# Schematic_-_Ebook_Reader_vFinal_v37.net
KiCad netlist of a schematic drawn in EAGLE
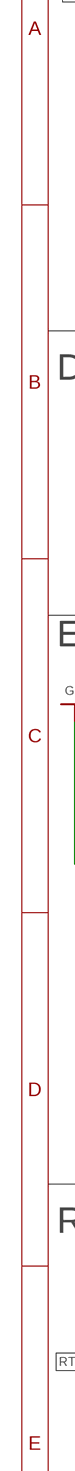
[diagram p0: schematic, sheet 1, part 1 of 2]
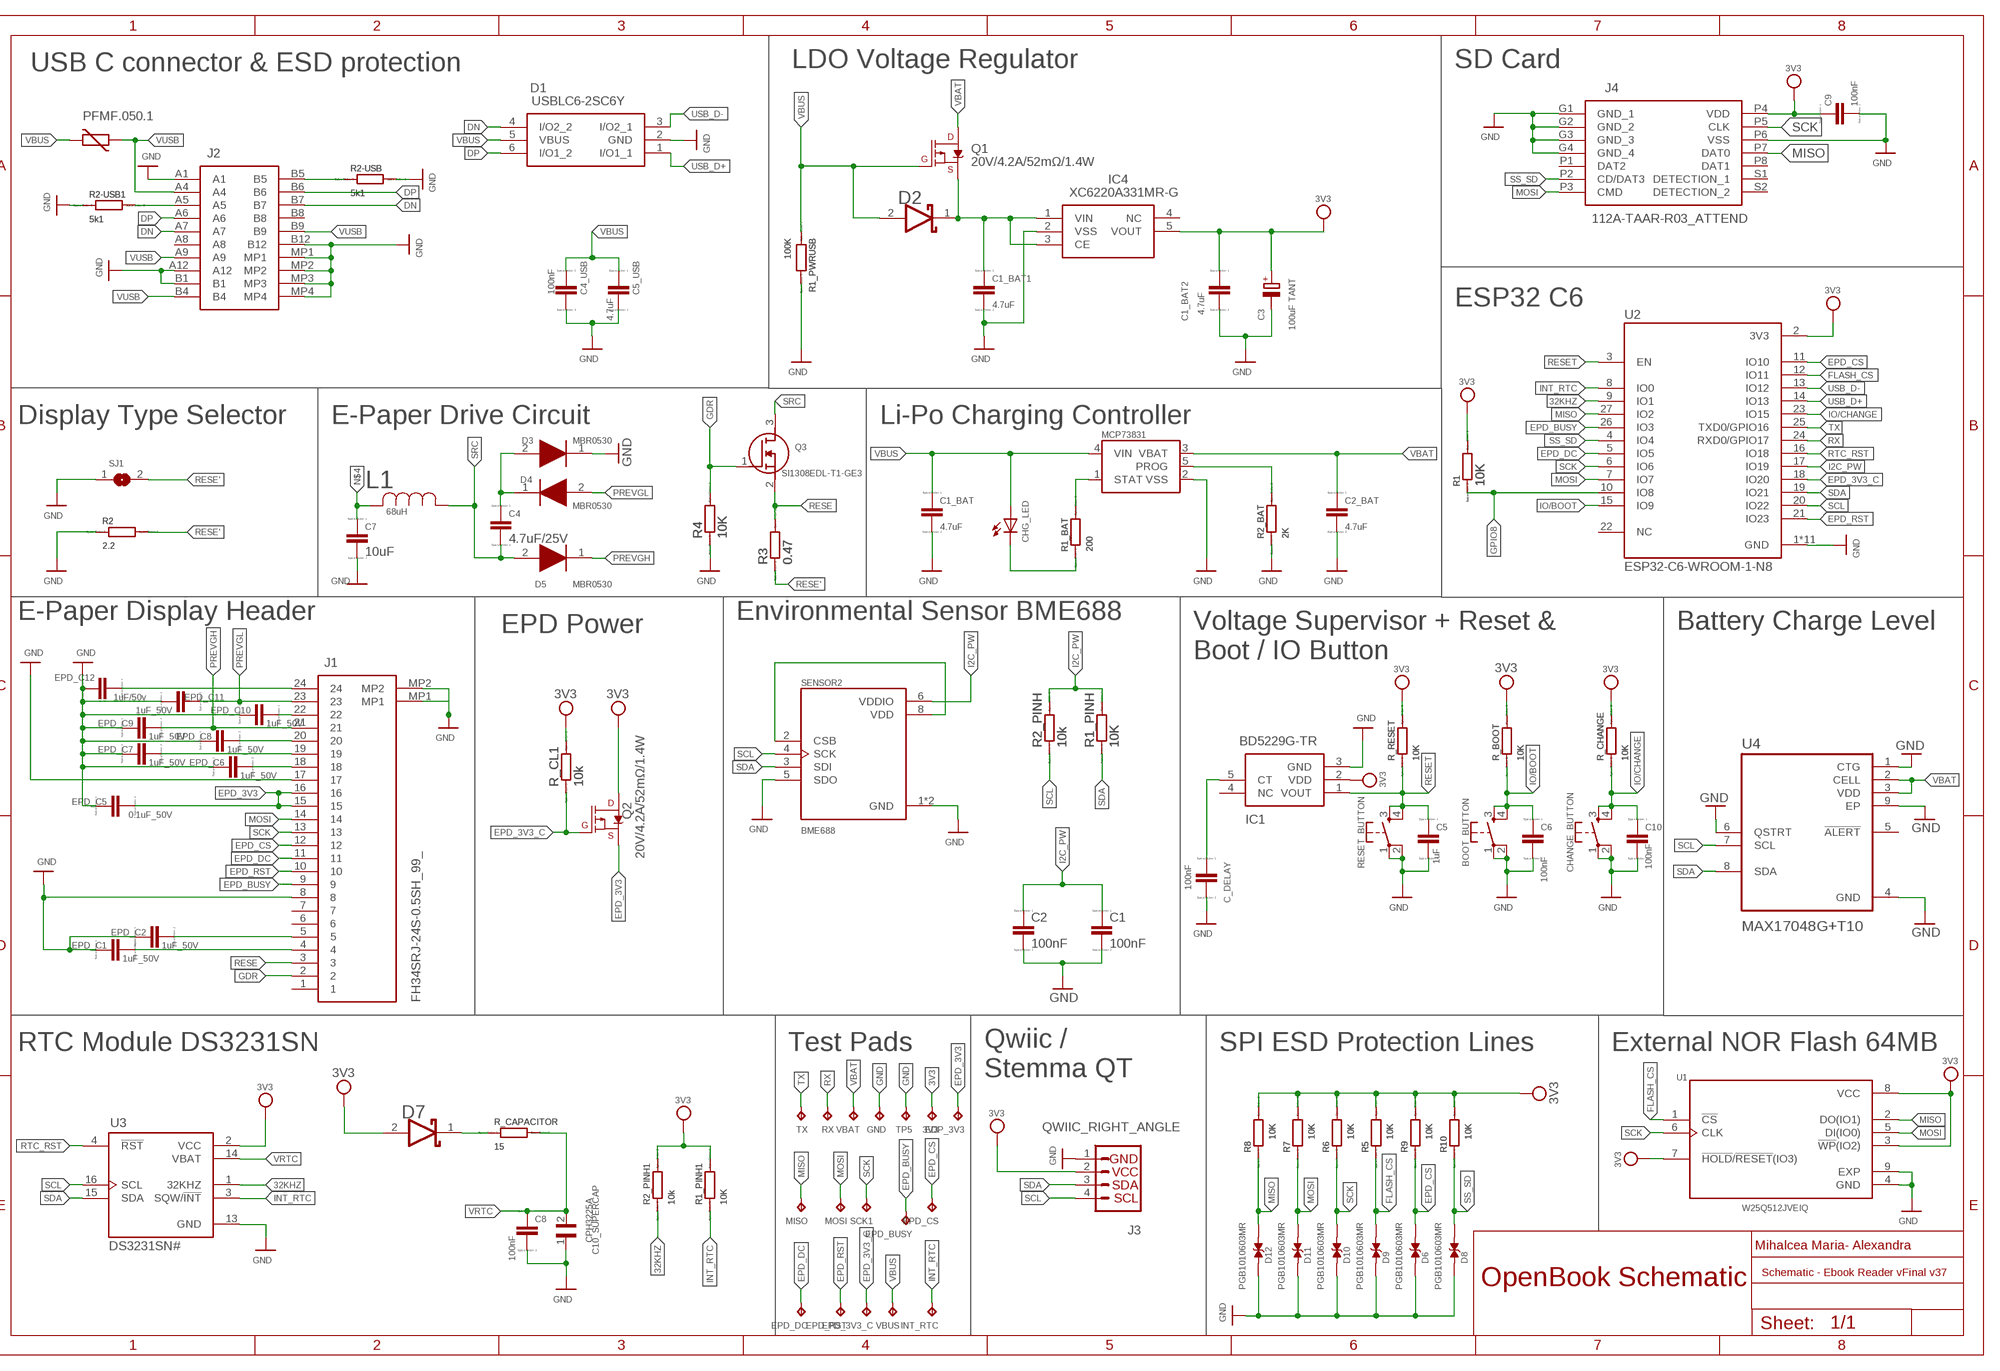
[diagram p1: schematic, sheet 1, part 2 of 2]

(export (version "E")
  (design (tool "Eeschema 10.0.6"))
  (components
    (comp (ref "3V3")
      (value "TPTP20R")
      (footprint "eagle-import:TP20R")
      (libsource (lib "eagle-import") (part "TPTP20R"))
    )
    (comp (ref "BOOT_BUTTON")
      (value "BUTTON_CUSYOMV1")
      (footprint "eagle-import:MYBUTTON")
      (libsource (lib "eagle-import") (part "BUTTON_CUSYOMV1"))
    )
    (comp (ref "C1")
      (value "100nF")
      (footprint "eagle-import:EAGLE-LTSPICE_C0402")
      (libsource (lib "eagle-import") (part "EAGLE-LTSPICE_CC0402"))
    )
    (comp (ref "C1_BAT")
      (value "4.7uF")
      (footprint "eagle-import:EAGLE-LTSPICE_C0402")
      (libsource (lib "eagle-import") (part "EAGLE-LTSPICE_CC0402"))
    )
    (comp (ref "C1_BAT1")
      (value "4.7uF")
      (footprint "eagle-import:EAGLE-LTSPICE_C0402")
      (libsource (lib "eagle-import") (part "EAGLE-LTSPICE_CC0402"))
    )
    (comp (ref "C1_BAT2")
      (value "4.7uF")
      (footprint "eagle-import:EAGLE-LTSPICE_C0402")
      (libsource (lib "eagle-import") (part "EAGLE-LTSPICE_CC0402"))
    )
    (comp (ref "C2")
      (value "100nF")
      (footprint "eagle-import:EAGLE-LTSPICE_C0402")
      (libsource (lib "eagle-import") (part "EAGLE-LTSPICE_CC0402"))
    )
    (comp (ref "C2_BAT")
      (value "4.7uF")
      (footprint "eagle-import:EAGLE-LTSPICE_C0402")
      (libsource (lib "eagle-import") (part "EAGLE-LTSPICE_CC0402"))
    )
    (comp (ref "C3")
      (value "100uF TANT")
      (footprint "eagle-import:RCL_CT3528")
      (libsource (lib "eagle-import") (part "RCL_CPOL-EUCT3528"))
    )
    (comp (ref "C4")
      (value "4.7uF/25V")
      (footprint "eagle-import:EAGLE-LTSPICE_C0402")
      (libsource (lib "eagle-import") (part "EAGLE-LTSPICE_CC0402"))
    )
    (comp (ref "C4_USB")
      (value "100nF")
      (footprint "eagle-import:EAGLE-LTSPICE_C0402")
      (libsource (lib "eagle-import") (part "EAGLE-LTSPICE_CC0402"))
    )
    (comp (ref "C5")
      (value "1uF")
      (footprint "eagle-import:EAGLE-LTSPICE_C0402")
      (libsource (lib "eagle-import") (part "EAGLE-LTSPICE_CC0402"))
    )
    (comp (ref "C5_USB")
      (value "4.7uF")
      (footprint "eagle-import:EAGLE-LTSPICE_C0402")
      (libsource (lib "eagle-import") (part "EAGLE-LTSPICE_CC0402"))
    )
    (comp (ref "C6")
      (value "100nF")
      (footprint "eagle-import:EAGLE-LTSPICE_C0402")
      (libsource (lib "eagle-import") (part "EAGLE-LTSPICE_CC0402"))
    )
    (comp (ref "C7")
      (value "10uF")
      (footprint "eagle-import:EAGLE-LTSPICE_C0402")
      (libsource (lib "eagle-import") (part "EAGLE-LTSPICE_CC0402"))
    )
    (comp (ref "C8")
      (value "100nF")
      (footprint "eagle-import:EAGLE-LTSPICE_C0402")
      (libsource (lib "eagle-import") (part "EAGLE-LTSPICE_CC0402"))
    )
    (comp (ref "C9")
      (value "100nF")
      (footprint "eagle-import:EAGLE-LTSPICE_C0402")
      (libsource (lib "eagle-import") (part "EAGLE-LTSPICE_CC0402"))
    )
    (comp (ref "C10")
      (value "100nF")
      (footprint "eagle-import:EAGLE-LTSPICE_C0402")
      (libsource (lib "eagle-import") (part "EAGLE-LTSPICE_CC0402"))
    )
    (comp (ref "C10_SUPERCAP")
      (value "CPH3225A")
      (footprint "eagle-import:CAPCP3225X100N")
      (fields (field (name "MF") "Seiko Instruments"))
      (libsource (lib "eagle-import") (part "CPH3225A"))
    )
    (comp (ref "CHANGE_BUTTON")
      (value "BUTTON_CUSYOMV1")
      (footprint "eagle-import:MYBUTTON")
      (libsource (lib "eagle-import") (part "BUTTON_CUSYOMV1"))
    )
    (comp (ref "CHG_LED")
      (value "ADAFRUIT_LEDCHIP-LED0603")
      (footprint "eagle-import:ADAFRUIT_CHIP-LED0603")
      (libsource (lib "eagle-import") (part "ADAFRUIT_LEDCHIP-LED0603"))
    )
    (comp (ref "C_DELAY")
      (value "100nF")
      (footprint "eagle-import:EAGLE-LTSPICE_C0402")
      (libsource (lib "eagle-import") (part "EAGLE-LTSPICE_CC0402"))
    )
    (comp (ref "D1")
      (value "USBLC6-2SC6Y")
      (footprint "eagle-import:SOT95P280X145-6N")
      (fields (field (name "MF") "STMicroelectronics"))
      (libsource (lib "eagle-import") (part "USBLC6-2SC6Y"))
    )
    (comp (ref "D2")
      (value "ESP32_WROVER_AVX---SD0805S020S1R0_AVX_SD0805S020S1R0_0_0AVX_SD0805S020S1R0_0_0")
      (footprint "eagle-import:ESP32_WROVER_AVX---SD0805S020S1R0_AVX_SD0805S020S1R0_0")
      (fields
        (field (name "DIGIKEY_PART_NUMBER") "478-7800-1-ND")
        (field (name "MF") "AVX")
        (field (name "MOUSER_PART_NUMBER") "581-SD0805S020S1R0")
      )
      (libsource (lib "eagle-import") (part "ESP32_WROVER_AVX---SD0805S020S1R0_AVX_SD0805S020S1R0_0_0AVX_SD0805S020S1R0_0_0"))
    )
    (comp (ref "D3")
      (value "MBR0530")
      (footprint "eagle-import:SOD3716X135N")
      (fields (field (name "MF") "ON Semiconductor"))
      (libsource (lib "eagle-import") (part "MBR0530"))
    )
    (comp (ref "D4")
      (value "MBR0530")
      (footprint "eagle-import:SOD3716X135N")
      (fields (field (name "MF") "ON Semiconductor"))
      (libsource (lib "eagle-import") (part "MBR0530"))
    )
    (comp (ref "D5")
      (value "MBR0530")
      (footprint "eagle-import:SOD3716X135N")
      (fields (field (name "MF") "ON Semiconductor"))
      (libsource (lib "eagle-import") (part "MBR0530"))
    )
    (comp (ref "D6")
      (value "PGB1010603MR")
      (footprint "eagle-import:DIOC1608X36N")
      (fields (field (name "MF") "Littelfuse Inc."))
      (libsource (lib "eagle-import") (part "PGB1010603MR"))
    )
    (comp (ref "D7")
      (value "ESP32_WROVER_AVX---SD0805S020S1R0_AVX_SD0805S020S1R0_0_0AVX_SD0805S020S1R0_0_0")
      (footprint "eagle-import:ESP32_WROVER_AVX---SD0805S020S1R0_AVX_SD0805S020S1R0_0")
      (fields
        (field (name "DIGIKEY_PART_NUMBER") "478-7800-1-ND")
        (field (name "MF") "AVX")
        (field (name "MOUSER_PART_NUMBER") "581-SD0805S020S1R0")
      )
      (libsource (lib "eagle-import") (part "ESP32_WROVER_AVX---SD0805S020S1R0_AVX_SD0805S020S1R0_0_0AVX_SD0805S020S1R0_0_0"))
    )
    (comp (ref "D8")
      (value "PGB1010603MR")
      (footprint "eagle-import:DIOC1608X36N")
      (fields (field (name "MF") "Littelfuse Inc."))
      (libsource (lib "eagle-import") (part "PGB1010603MR"))
    )
    (comp (ref "D9")
      (value "PGB1010603MR")
      (footprint "eagle-import:DIOC1608X36N")
      (fields (field (name "MF") "Littelfuse Inc."))
      (libsource (lib "eagle-import") (part "PGB1010603MR"))
    )
    (comp (ref "D10")
      (value "PGB1010603MR")
      (footprint "eagle-import:DIOC1608X36N")
      (fields (field (name "MF") "Littelfuse Inc."))
      (libsource (lib "eagle-import") (part "PGB1010603MR"))
    )
    (comp (ref "D11")
      (value "PGB1010603MR")
      (footprint "eagle-import:DIOC1608X36N")
      (fields (field (name "MF") "Littelfuse Inc."))
      (libsource (lib "eagle-import") (part "PGB1010603MR"))
    )
    (comp (ref "D12")
      (value "PGB1010603MR")
      (footprint "eagle-import:DIOC1608X36N")
      (fields (field (name "MF") "Littelfuse Inc."))
      (libsource (lib "eagle-import") (part "PGB1010603MR"))
    )
    (comp (ref "EDP_3V3")
      (value "TPTP20R")
      (footprint "eagle-import:TP20R")
      (libsource (lib "eagle-import") (part "TPTP20R"))
    )
    (comp (ref "EPD_3V3_C")
      (value "TPTP20R")
      (footprint "eagle-import:TP20R")
      (libsource (lib "eagle-import") (part "TPTP20R"))
    )
    (comp (ref "EPD_BUSY")
      (value "TPTP20R")
      (footprint "eagle-import:TP20R")
      (libsource (lib "eagle-import") (part "TPTP20R"))
    )
    (comp (ref "EPD_C1")
      (value "1uF_50V")
      (footprint "eagle-import:EAGLE-LTSPICE_C0402")
      (libsource (lib "eagle-import") (part "EAGLE-LTSPICE_CC0402"))
    )
    (comp (ref "EPD_C2")
      (value "1uF_50V")
      (footprint "eagle-import:EAGLE-LTSPICE_C0402")
      (libsource (lib "eagle-import") (part "EAGLE-LTSPICE_CC0402"))
    )
    (comp (ref "EPD_C5")
      (value "0.1uF_50V")
      (footprint "eagle-import:EAGLE-LTSPICE_C0402")
      (libsource (lib "eagle-import") (part "EAGLE-LTSPICE_CC0402"))
    )
    (comp (ref "EPD_C6")
      (value "1uF_50V")
      (footprint "eagle-import:EAGLE-LTSPICE_C0402")
      (libsource (lib "eagle-import") (part "EAGLE-LTSPICE_CC0402"))
    )
    (comp (ref "EPD_C7")
      (value "1uF_50V")
      (footprint "eagle-import:EAGLE-LTSPICE_C0402")
      (libsource (lib "eagle-import") (part "EAGLE-LTSPICE_CC0402"))
    )
    (comp (ref "EPD_C8")
      (value "1uF_50V")
      (footprint "eagle-import:EAGLE-LTSPICE_C0402")
      (libsource (lib "eagle-import") (part "EAGLE-LTSPICE_CC0402"))
    )
    (comp (ref "EPD_C9")
      (value "1uF_50V")
      (footprint "eagle-import:EAGLE-LTSPICE_C0402")
      (libsource (lib "eagle-import") (part "EAGLE-LTSPICE_CC0402"))
    )
    (comp (ref "EPD_C10")
      (value "1uF_50V")
      (footprint "eagle-import:EAGLE-LTSPICE_C0402")
      (libsource (lib "eagle-import") (part "EAGLE-LTSPICE_CC0402"))
    )
    (comp (ref "EPD_C11")
      (value "1uF_50V")
      (footprint "eagle-import:EAGLE-LTSPICE_C0402")
      (libsource (lib "eagle-import") (part "EAGLE-LTSPICE_CC0402"))
    )
    (comp (ref "EPD_C12")
      (value "1uF/50v")
      (footprint "eagle-import:EAGLE-LTSPICE_C0402")
      (libsource (lib "eagle-import") (part "EAGLE-LTSPICE_CC0402"))
    )
    (comp (ref "EPD_CS")
      (value "TPTP20R")
      (footprint "eagle-import:TP20R")
      (libsource (lib "eagle-import") (part "TPTP20R"))
    )
    (comp (ref "EPD_DC")
      (value "TPTP20R")
      (footprint "eagle-import:TP20R")
      (libsource (lib "eagle-import") (part "TPTP20R"))
    )
    (comp (ref "EPD_RST")
      (value "TPTP20R")
      (footprint "eagle-import:TP20R")
      (libsource (lib "eagle-import") (part "TPTP20R"))
    )
    (comp (ref "GND")
      (value "TPTP20R")
      (footprint "eagle-import:TP20R")
      (libsource (lib "eagle-import") (part "TPTP20R"))
    )
    (comp (ref "IC1")
      (value "BD5229G-TR")
      (footprint "eagle-import:SOT95P280X125-5N")
      (fields (field (name "MOUSER_PART_NUMBER") "755-BD5229G-TR"))
      (libsource (lib "eagle-import") (part "BD5229G-TR"))
    )
    (comp (ref "IC4")
      (value "XC6220A331MR-G")
      (footprint "eagle-import:SOT95P280X120-5N")
      (fields (field (name "MOUSER_PART_NUMBER") "865-XC6220A331MR-G"))
      (libsource (lib "eagle-import") (part "XC6220A331MR-G"))
    )
    (comp (ref "INT_RTC")
      (value "TPTP20R")
      (footprint "eagle-import:TP20R")
      (libsource (lib "eagle-import") (part "TPTP20R"))
    )
    (comp (ref "J1")
      (value "FH34SRJ-24S-0.5SH_99_")
      (footprint "eagle-import:FH34SRJ24S05SH99")
      (fields
        (field (name "MANUFACTURER_PART_NUMBER") "FH34SRJ-24S-0.5SH(99)")
        (field (name "MOUSER_PART_NUMBER") "798-FH34SRJ24S05SH99")
      )
      (libsource (lib "eagle-import") (part "FH34SRJ-24S-0.5SH_99_"))
    )
    (comp (ref "J2")
      (value "SAMACSYS_PARTS_USB4110-GF-A")
      (footprint "eagle-import:SAMACSYS_PARTS_USB4110GFA")
      (fields
        (field (name "MANUFACTURER_PART_NUMBER") "USB4110-GF-A")
        (field (name "MOUSER_PART_NUMBER") "640-USB4110-GF-A")
      )
      (libsource (lib "eagle-import") (part "SAMACSYS_PARTS_USB4110-GF-A"))
    )
    (comp (ref "J3")
      (value "QWIIC_RIGHT_ANGLE")
      (footprint "eagle-import:JST04_1MM_RA")
      (libsource (lib "eagle-import") (part "QWIIC_CONNECTORJS-1MM"))
    )
    (comp (ref "J4")
      (value "112A-TAAR-R03_ATTEND")
      (footprint "eagle-import:112ATAARR03ATTEND")
      (fields (field (name "MANUFACTURER_PART_NUMBER") "112A-TAAR-R03 ATTEND"))
      (libsource (lib "eagle-import") (part "112A-TAAR-R03_ATTEND"))
    )
    (comp (ref "L1")
      (value "68uH")
      (footprint "eagle-import:IND_4828-WE-TPC_WRE")
      (fields
        (field (name "MANUFACTURER_PART_NUMBER") "744043680")
        (field (name "COPYRIGHT") "Copyright (C) 2024 Ultra Librarian. All rights reserved.")
      )
      (libsource (lib "eagle-import") (part "744043680IND_4828-WE-TPC_WRE"))
    )
    (comp (ref "MCP73831")
      (value "ESP32_WROVER_SPARKFUN-IC-POWER_MCP73831")
      (footprint "eagle-import:ESP32_WROVER_SPARKFUN-IC-POWER_SOT23-5")
      (libsource (lib "eagle-import") (part "ESP32_WROVER_SPARKFUN-IC-POWER_MCP73831"))
    )
    (comp (ref "MISO")
      (value "TPTP20R")
      (footprint "eagle-import:TP20R")
      (libsource (lib "eagle-import") (part "TPTP20R"))
    )
    (comp (ref "MOSI")
      (value "TPTP20R")
      (footprint "eagle-import:TP20R")
      (libsource (lib "eagle-import") (part "TPTP20R"))
    )
    (comp (ref "PFMF.050.1")
      (value "ESP32C6_VARISTORCN1812")
      (footprint "eagle-import:ESP32C6_VARISTOR_CT_CN1812")
      (libsource (lib "eagle-import") (part "ESP32C6_VARISTORCN1812"))
    )
    (comp (ref "Q1")
      (value "20V/4.2A/52mΩ/1.4W")
      (footprint "eagle-import:ESP32_WROVER_SPARKFUN-DISCRETESEMI_SOT23-3")
      (libsource (lib "eagle-import") (part "ESP32_WROVER_SPARKFUN-DISCRETESEMI_MOSFET_PCH-DMG2305UX-7"))
    )
    (comp (ref "Q2")
      (value "20V/4.2A/52mΩ/1.4W")
      (footprint "eagle-import:ESP32_WROVER_SPARKFUN-DISCRETESEMI_SOT23-3")
      (libsource (lib "eagle-import") (part "ESP32_WROVER_SPARKFUN-DISCRETESEMI_MOSFET_PCH-DMG2305UX-7"))
    )
    (comp (ref "Q3")
      (value "SI1308EDL-T1-GE3")
      (footprint "eagle-import:SOT65P210X110-3N")
      (fields (field (name "MF") "Vishay Siliconix"))
      (libsource (lib "eagle-import") (part "SI1308EDL-T1-GE3"))
    )
    (comp (ref "R1")
      (value "10K")
      (footprint "eagle-import:ESP32_WROVER_EAGLE-LTSPICE_R0402")
      (libsource (lib "eagle-import") (part "ESP32_WROVER_EAGLE-LTSPICE_RR0402"))
    )
    (comp (ref "R1_BAT")
      (value "200")
      (footprint "eagle-import:ESP32_WROVER_EAGLE-LTSPICE_R0402")
      (libsource (lib "eagle-import") (part "ESP32_WROVER_EAGLE-LTSPICE_RR0402"))
    )
    (comp (ref "R1_PINH")
      (value "10K")
      (footprint "eagle-import:ESP32_WROVER_EAGLE-LTSPICE_R0402")
      (libsource (lib "eagle-import") (part "ESP32_WROVER_EAGLE-LTSPICE_RR0402"))
    )
    (comp (ref "R1_PINH1")
      (value "10K")
      (footprint "eagle-import:ESP32_WROVER_EAGLE-LTSPICE_R0402")
      (libsource (lib "eagle-import") (part "ESP32_WROVER_EAGLE-LTSPICE_RR0402"))
    )
    (comp (ref "R1_PWRUSB")
      (value "100K")
      (footprint "eagle-import:ESP32_WROVER_EAGLE-LTSPICE_R0402")
      (libsource (lib "eagle-import") (part "ESP32_WROVER_EAGLE-LTSPICE_RR0402"))
    )
    (comp (ref "R2")
      (value "2.2")
      (footprint "eagle-import:ESP32_WROVER_EAGLE-LTSPICE_R0402")
      (libsource (lib "eagle-import") (part "ESP32_WROVER_EAGLE-LTSPICE_RR0402"))
    )
    (comp (ref "R2-USB")
      (value "5k1")
      (footprint "eagle-import:ESP32_WROVER_EAGLE-LTSPICE_R0402")
      (libsource (lib "eagle-import") (part "ESP32_WROVER_EAGLE-LTSPICE_RR0402"))
    )
    (comp (ref "R2-USB1")
      (value "5k1")
      (footprint "eagle-import:ESP32_WROVER_EAGLE-LTSPICE_R0402")
      (libsource (lib "eagle-import") (part "ESP32_WROVER_EAGLE-LTSPICE_RR0402"))
    )
    (comp (ref "R2_BAT")
      (value "2K")
      (footprint "eagle-import:ESP32_WROVER_EAGLE-LTSPICE_R0402")
      (libsource (lib "eagle-import") (part "ESP32_WROVER_EAGLE-LTSPICE_RR0402"))
    )
    (comp (ref "R2_PINH")
      (value "10k")
      (footprint "eagle-import:ESP32_WROVER_EAGLE-LTSPICE_R0402")
      (libsource (lib "eagle-import") (part "ESP32_WROVER_EAGLE-LTSPICE_RR0402"))
    )
    (comp (ref "R2_PINH1")
      (value "10k")
      (footprint "eagle-import:ESP32_WROVER_EAGLE-LTSPICE_R0402")
      (libsource (lib "eagle-import") (part "ESP32_WROVER_EAGLE-LTSPICE_RR0402"))
    )
    (comp (ref "R3")
      (value "0.47")
      (footprint "eagle-import:ESP32_WROVER_EAGLE-LTSPICE_R0402")
      (libsource (lib "eagle-import") (part "ESP32_WROVER_EAGLE-LTSPICE_RR0402"))
    )
    (comp (ref "R4")
      (value "10K")
      (footprint "eagle-import:ESP32_WROVER_EAGLE-LTSPICE_R0402")
      (libsource (lib "eagle-import") (part "ESP32_WROVER_EAGLE-LTSPICE_RR0402"))
    )
    (comp (ref "R5")
      (value "10K")
      (footprint "eagle-import:ESP32_WROVER_EAGLE-LTSPICE_R0402")
      (libsource (lib "eagle-import") (part "ESP32_WROVER_EAGLE-LTSPICE_RR0402"))
    )
    (comp (ref "R6")
      (value "10K")
      (footprint "eagle-import:ESP32_WROVER_EAGLE-LTSPICE_R0402")
      (libsource (lib "eagle-import") (part "ESP32_WROVER_EAGLE-LTSPICE_RR0402"))
    )
    (comp (ref "R7")
      (value "10K")
      (footprint "eagle-import:ESP32_WROVER_EAGLE-LTSPICE_R0402")
      (libsource (lib "eagle-import") (part "ESP32_WROVER_EAGLE-LTSPICE_RR0402"))
    )
    (comp (ref "R8")
      (value "10K")
      (footprint "eagle-import:ESP32_WROVER_EAGLE-LTSPICE_R0402")
      (libsource (lib "eagle-import") (part "ESP32_WROVER_EAGLE-LTSPICE_RR0402"))
    )
    (comp (ref "R9")
      (value "10K")
      (footprint "eagle-import:ESP32_WROVER_EAGLE-LTSPICE_R0402")
      (libsource (lib "eagle-import") (part "ESP32_WROVER_EAGLE-LTSPICE_RR0402"))
    )
    (comp (ref "R10")
      (value "10K")
      (footprint "eagle-import:ESP32_WROVER_EAGLE-LTSPICE_R0402")
      (libsource (lib "eagle-import") (part "ESP32_WROVER_EAGLE-LTSPICE_RR0402"))
    )
    (comp (ref "RESET_BUTTON")
      (value "BUTTON_CUSYOMV1")
      (footprint "eagle-import:MYBUTTON")
      (libsource (lib "eagle-import") (part "BUTTON_CUSYOMV1"))
    )
    (comp (ref "RX")
      (value "TPTP20R")
      (footprint "eagle-import:TP20R")
      (libsource (lib "eagle-import") (part "TPTP20R"))
    )
    (comp (ref "R_BOOT")
      (value "10K")
      (footprint "eagle-import:ESP32_WROVER_EAGLE-LTSPICE_R0402")
      (libsource (lib "eagle-import") (part "ESP32_WROVER_EAGLE-LTSPICE_RR0402"))
    )
    (comp (ref "R_CAPACITOR")
      (value "15")
      (footprint "eagle-import:ESP32_WROVER_EAGLE-LTSPICE_R0402")
      (libsource (lib "eagle-import") (part "ESP32_WROVER_EAGLE-LTSPICE_RR0402"))
    )
    (comp (ref "R_CHANGE")
      (value "10K")
      (footprint "eagle-import:ESP32_WROVER_EAGLE-LTSPICE_R0402")
      (libsource (lib "eagle-import") (part "ESP32_WROVER_EAGLE-LTSPICE_RR0402"))
    )
    (comp (ref "R_CL1")
      (value "10k")
      (footprint "eagle-import:ESP32_WROVER_EAGLE-LTSPICE_R0402")
      (libsource (lib "eagle-import") (part "ESP32_WROVER_EAGLE-LTSPICE_RR0402"))
    )
    (comp (ref "R_RESET")
      (value "10K")
      (footprint "eagle-import:ESP32_WROVER_EAGLE-LTSPICE_R0402")
      (libsource (lib "eagle-import") (part "ESP32_WROVER_EAGLE-LTSPICE_RR0402"))
    )
    (comp (ref "SCK1")
      (value "TPTP20R")
      (footprint "eagle-import:TP20R")
      (libsource (lib "eagle-import") (part "TPTP20R"))
    )
    (comp (ref "SENSOR2")
      (value "BME688")
      (footprint "eagle-import:ESP32_WROVER_BME680_PSON80P300X300X100-8N")
      (fields (field (name "MF") "Bosch Sensortec") (field (name "MP") "BME680"))
      (libsource (lib "eagle-import") (part "ESP32_WROVER_BME680_BME680"))
    )
    (comp (ref "SJ1") (value "SJ") (footprint "eagle-import:SJ") (libsource (lib "eagle-import") (part "SJ")))
    (comp (ref "TP5")
      (value "TPTP20R")
      (footprint "eagle-import:TP20R")
      (libsource (lib "eagle-import") (part "TPTP20R"))
    )
    (comp (ref "TX")
      (value "TPTP20R")
      (footprint "eagle-import:TP20R")
      (libsource (lib "eagle-import") (part "TPTP20R"))
    )
    (comp (ref "U1")
      (value "W25Q512JVEIQ")
      (footprint "eagle-import:SON127P600X800X80-9N")
      (fields (field (name "MF") "Winbond Electronics"))
      (libsource (lib "eagle-import") (part "W25Q512JVEIQ"))
    )
    (comp (ref "U2")
      (value "ESP32-C6-WROOM-1-N8")
      (footprint "eagle-import:XCVR_ESP32-C6-WROOM-1-N8")
      (fields (field (name "MF") "Espressif Systems"))
      (libsource (lib "eagle-import") (part "ESP32-C6-WROOM-1-N8"))
    )
    (comp (ref "U3")
      (value "DS3231SN#")
      (footprint "eagle-import:SOIC127P1032X265-16N")
      (fields (field (name "MF") "Analog Devices"))
      (libsource (lib "eagle-import") (part "DS3231SN#"))
    )
    (comp (ref "U4")
      (value "MAX17048G+T10")
      (footprint "eagle-import:SON50P200X200X80-9N")
      (fields (field (name "MF") "Analog Devices"))
      (libsource (lib "eagle-import") (part "MAX17048G+T10"))
    )
    (comp (ref "VBAT")
      (value "TPTP20R")
      (footprint "eagle-import:TP20R")
      (libsource (lib "eagle-import") (part "TPTP20R"))
    )
    (comp (ref "VBUS")
      (value "TPTP20R")
      (footprint "eagle-import:TP20R")
      (libsource (lib "eagle-import") (part "TPTP20R"))
    )
  )
  (nets
    (net (code "1") (name "3V3") (class "Default")
      (node (ref "3V3") (pin "TP") (pinfunction "TP_TP") (pintype "input"))
      (node (ref "C1_BAT2") (pin "1") (pinfunction "1_1") (pintype "passive"))
      (node (ref "C3") (pin "+") (pinfunction "+_+") (pintype "passive"))
      (node (ref "C9") (pin "1") (pinfunction "1_1") (pintype "passive"))
      (node (ref "D7") (pin "2") (pinfunction "ANODE_2") (pintype "bidirectional"))
      (node (ref "IC1") (pin "2") (pinfunction "VDD_2") (pintype "bidirectional"))
      (node (ref "IC4") (pin "5") (pinfunction "VOUT_5") (pintype "bidirectional"))
      (node (ref "J3") (pin "2") (pinfunction "2_2") (pintype "power_in"))
      (node (ref "J4") (pin "P4") (pinfunction "VDD_P4") (pintype "bidirectional"))
      (node (ref "Q2") (pin "3") (pinfunction "D_3") (pintype "bidirectional"))
      (node (ref "R1") (pin "2") (pinfunction "2_2") (pintype "passive"))
      (node (ref "R10") (pin "2") (pinfunction "2_2") (pintype "passive"))
      (node (ref "R1_PINH1") (pin "2") (pinfunction "2_2") (pintype "passive"))
      (node (ref "R2_PINH1") (pin "2") (pinfunction "2_2") (pintype "passive"))
      (node (ref "R5") (pin "2") (pinfunction "2_2") (pintype "passive"))
      (node (ref "R6") (pin "2") (pinfunction "2_2") (pintype "passive"))
      (node (ref "R7") (pin "2") (pinfunction "2_2") (pintype "passive"))
      (node (ref "R8") (pin "2") (pinfunction "2_2") (pintype "passive"))
      (node (ref "R9") (pin "2") (pinfunction "2_2") (pintype "passive"))
      (node (ref "R_BOOT") (pin "2") (pinfunction "2_2") (pintype "passive"))
      (node (ref "R_CHANGE") (pin "2") (pinfunction "2_2") (pintype "passive"))
      (node (ref "R_CL1") (pin "2") (pinfunction "2_2") (pintype "passive"))
      (node (ref "R_RESET") (pin "2") (pinfunction "2_2") (pintype "passive"))
      (node (ref "U1") (pin "3") (pinfunction "~{WP}(IO2)_3") (pintype "bidirectional"))
      (node (ref "U1") (pin "7") (pinfunction "~{HOLD}/~{RESET}(IO3)_7") (pintype "bidirectional"))
      (node (ref "U1") (pin "8") (pinfunction "VCC_8") (pintype "power_in"))
      (node (ref "U2") (pin "2") (pinfunction "3V3_2") (pintype "power_in"))
      (node (ref "U3") (pin "2") (pinfunction "VCC_2") (pintype "power_in"))
    )
    (net (code "2") (name "32KHZ") (class "Default")
      (node (ref "R2_PINH1") (pin "1") (pinfunction "1_1") (pintype "passive"))
      (node (ref "U2") (pin "9") (pinfunction "IO1_9") (pintype "bidirectional"))
      (node (ref "U3") (pin "1") (pinfunction "32KHZ_1") (pintype "output"))
    )
    (net (code "3") (name "DN") (class "Default")
      (node (ref "D1") (pin "4") (pinfunction "I/O2_2_4") (pintype "bidirectional"))
      (node (ref "J2") (pin "A7") (pinfunction "A7_A7") (pintype "bidirectional"))
      (node (ref "J2") (pin "B7") (pinfunction "B7_B7") (pintype "bidirectional"))
    )
    (net (code "4") (name "DP") (class "Default")
      (node (ref "D1") (pin "6") (pinfunction "I/O1_2_6") (pintype "bidirectional"))
      (node (ref "J2") (pin "A6") (pinfunction "A6_A6") (pintype "bidirectional"))
      (node (ref "J2") (pin "B6") (pinfunction "B6_B6") (pintype "bidirectional"))
    )
    (net (code "5") (name "EPD_3V3") (class "Default")
      (node (ref "EDP_3V3") (pin "TP") (pinfunction "TP_TP") (pintype "input"))
      (node (ref "EPD_C5") (pin "2") (pinfunction "2_2") (pintype "passive"))
      (node (ref "J1") (pin "15") (pinfunction "15_15") (pintype "bidirectional"))
      (node (ref "J1") (pin "16") (pinfunction "16_16") (pintype "bidirectional"))
      (node (ref "Q2") (pin "2") (pinfunction "S_2") (pintype "bidirectional"))
    )
    (net (code "6") (name "EPD_3V3_C") (class "Default")
      (node (ref "EPD_3V3_C") (pin "TP") (pinfunction "TP_TP") (pintype "input"))
      (node (ref "Q2") (pin "1") (pinfunction "G_1") (pintype "bidirectional"))
      (node (ref "R_CL1") (pin "1") (pinfunction "1_1") (pintype "passive"))
      (node (ref "U2") (pin "18") (pinfunction "IO20_18") (pintype "bidirectional"))
    )
    (net (code "7") (name "EPD_BUSY") (class "Default")
      (node (ref "EPD_BUSY") (pin "TP") (pinfunction "TP_TP") (pintype "input"))
      (node (ref "J1") (pin "9") (pinfunction "9_9") (pintype "bidirectional"))
      (node (ref "U2") (pin "26") (pinfunction "IO3_26") (pintype "bidirectional"))
    )
    (net (code "8") (name "EPD_CS") (class "Default")
      (node (ref "D6") (pin "2") (pinfunction "2_2") (pintype "passive"))
      (node (ref "EPD_CS") (pin "TP") (pinfunction "TP_TP") (pintype "input"))
      (node (ref "J1") (pin "12") (pinfunction "12_12") (pintype "bidirectional"))
      (node (ref "R9") (pin "1") (pinfunction "1_1") (pintype "passive"))
      (node (ref "U2") (pin "11") (pinfunction "IO10_11") (pintype "bidirectional"))
    )
    (net (code "9") (name "EPD_DC") (class "Default")
      (node (ref "EPD_DC") (pin "TP") (pinfunction "TP_TP") (pintype "input"))
      (node (ref "J1") (pin "11") (pinfunction "11_11") (pintype "bidirectional"))
      (node (ref "U2") (pin "5") (pinfunction "IO5_5") (pintype "bidirectional"))
    )
    (net (code "10") (name "EPD_RST") (class "Default")
      (node (ref "EPD_RST") (pin "TP") (pinfunction "TP_TP") (pintype "input"))
      (node (ref "J1") (pin "10") (pinfunction "10_10") (pintype "bidirectional"))
      (node (ref "U2") (pin "21") (pinfunction "IO23_21") (pintype "bidirectional"))
    )
    (net (code "11") (name "FLASH_CS") (class "Default")
      (node (ref "D9") (pin "2") (pinfunction "2_2") (pintype "passive"))
      (node (ref "R5") (pin "1") (pinfunction "1_1") (pintype "passive"))
      (node (ref "U1") (pin "1") (pinfunction "~{CS}_1") (pintype "input"))
      (node (ref "U2") (pin "12") (pinfunction "IO11_12") (pintype "bidirectional"))
    )
    (net (code "12") (name "GDR") (class "Default")
      (node (ref "J1") (pin "2") (pinfunction "2_2") (pintype "bidirectional"))
      (node (ref "Q3") (pin "1") (pinfunction "G_1") (pintype "bidirectional"))
      (node (ref "R4") (pin "2") (pinfunction "2_2") (pintype "passive"))
    )
    (net (code "13") (name "GND") (class "Default")
      (node (ref "BOOT_BUTTON") (pin "1") (pinfunction "1_1") (pintype "passive"))
      (node (ref "BOOT_BUTTON") (pin "2") (pinfunction "2_2") (pintype "passive"))
      (node (ref "C1") (pin "2") (pinfunction "2_2") (pintype "passive"))
      (node (ref "C10") (pin "2") (pinfunction "2_2") (pintype "passive"))
      (node (ref "C10_SUPERCAP") (pin "1") (pinfunction "1_1") (pintype "passive"))
      (node (ref "C1_BAT") (pin "2") (pinfunction "2_2") (pintype "passive"))
      (node (ref "C1_BAT1") (pin "2") (pinfunction "2_2") (pintype "passive"))
      (node (ref "C1_BAT2") (pin "2") (pinfunction "2_2") (pintype "passive"))
      (node (ref "C2") (pin "2") (pinfunction "2_2") (pintype "passive"))
      (node (ref "C2_BAT") (pin "2") (pinfunction "2_2") (pintype "passive"))
      (node (ref "C3") (pin "-") (pinfunction "-_-") (pintype "passive"))
      (node (ref "C4_USB") (pin "2") (pinfunction "2_2") (pintype "passive"))
      (node (ref "C5") (pin "2") (pinfunction "2_2") (pintype "passive"))
      (node (ref "C5_USB") (pin "2") (pinfunction "2_2") (pintype "passive"))
      (node (ref "C6") (pin "2") (pinfunction "2_2") (pintype "passive"))
      (node (ref "C7") (pin "2") (pinfunction "2_2") (pintype "passive"))
      (node (ref "C8") (pin "2") (pinfunction "2_2") (pintype "passive"))
      (node (ref "C9") (pin "2") (pinfunction "2_2") (pintype "passive"))
      (node (ref "CHANGE_BUTTON") (pin "1") (pinfunction "1_1") (pintype "passive"))
      (node (ref "CHANGE_BUTTON") (pin "2") (pinfunction "2_2") (pintype "passive"))
      (node (ref "C_DELAY") (pin "2") (pinfunction "2_2") (pintype "passive"))
      (node (ref "D1") (pin "2") (pinfunction "GND_2") (pintype "bidirectional"))
      (node (ref "D10") (pin "1") (pinfunction "1_1") (pintype "passive"))
      (node (ref "D11") (pin "1") (pinfunction "1_1") (pintype "passive"))
      (node (ref "D12") (pin "1") (pinfunction "1_1") (pintype "passive"))
      (node (ref "D3") (pin "1") (pinfunction "K_1") (pintype "bidirectional"))
      (node (ref "D6") (pin "1") (pinfunction "1_1") (pintype "passive"))
      (node (ref "D8") (pin "1") (pinfunction "1_1") (pintype "passive"))
      (node (ref "D9") (pin "1") (pinfunction "1_1") (pintype "passive"))
      (node (ref "EPD_C1") (pin "1") (pinfunction "1_1") (pintype "passive"))
      (node (ref "EPD_C10") (pin "1") (pinfunction "1_1") (pintype "passive"))
      (node (ref "EPD_C11") (pin "1") (pinfunction "1_1") (pintype "passive"))
      (node (ref "EPD_C12") (pin "1") (pinfunction "1_1") (pintype "passive"))
      (node (ref "EPD_C2") (pin "1") (pinfunction "1_1") (pintype "passive"))
      (node (ref "EPD_C5") (pin "1") (pinfunction "1_1") (pintype "passive"))
      (node (ref "EPD_C6") (pin "1") (pinfunction "1_1") (pintype "passive"))
      (node (ref "EPD_C7") (pin "1") (pinfunction "1_1") (pintype "passive"))
      (node (ref "EPD_C8") (pin "1") (pinfunction "1_1") (pintype "passive"))
      (node (ref "EPD_C9") (pin "1") (pinfunction "1_1") (pintype "passive"))
      (node (ref "GND") (pin "TP") (pinfunction "TP_TP") (pintype "input"))
      (node (ref "IC1") (pin "3") (pinfunction "GND_3") (pintype "bidirectional"))
      (node (ref "IC4") (pin "2") (pinfunction "VSS_2") (pintype "bidirectional"))
      (node (ref "J1") (pin "17") (pinfunction "17_17") (pintype "bidirectional"))
      (node (ref "J1") (pin "8") (pinfunction "8_8") (pintype "bidirectional"))
      (node (ref "J1") (pin "MP1") (pinfunction "MP1_MP1") (pintype "bidirectional"))
      (node (ref "J1") (pin "MP2") (pinfunction "MP2_MP2") (pintype "bidirectional"))
      (node (ref "J2") (pin "A1") (pinfunction "A1_A1") (pintype "bidirectional"))
      (node (ref "J2") (pin "A12") (pinfunction "A12_A12") (pintype "bidirectional"))
      (node (ref "J2") (pin "B1") (pinfunction "B1_B1") (pintype "bidirectional"))
      (node (ref "J2") (pin "B12") (pinfunction "B12_B12") (pintype "bidirectional"))
      (node (ref "J2") (pin "MP1") (pinfunction "MP1_MP1") (pintype "bidirectional"))
      (node (ref "J2") (pin "MP2") (pinfunction "MP2_MP2") (pintype "bidirectional"))
      (node (ref "J2") (pin "MP3") (pinfunction "MP3_MP3") (pintype "bidirectional"))
      (node (ref "J2") (pin "MP4") (pinfunction "MP4_MP4") (pintype "bidirectional"))
      (node (ref "J3") (pin "1") (pinfunction "1_1") (pintype "power_in"))
      (node (ref "J4") (pin "G1") (pinfunction "GND_1_G1") (pintype "bidirectional"))
      (node (ref "J4") (pin "G2") (pinfunction "GND_2_G2") (pintype "bidirectional"))
      (node (ref "J4") (pin "G3") (pinfunction "GND_3_G3") (pintype "bidirectional"))
      (node (ref "J4") (pin "G4") (pinfunction "GND_4_G4") (pintype "bidirectional"))
      (node (ref "J4") (pin "P6") (pinfunction "VSS_P6") (pintype "bidirectional"))
      (node (ref "MCP73831") (pin "2") (pinfunction "VSS_2") (pintype "power_in"))
      (node (ref "R1_PWRUSB") (pin "2") (pinfunction "2_2") (pintype "passive"))
      (node (ref "R2") (pin "1") (pinfunction "1_1") (pintype "passive"))
      (node (ref "R2-USB") (pin "2") (pinfunction "2_2") (pintype "passive"))
      (node (ref "R2-USB1") (pin "1") (pinfunction "1_1") (pintype "passive"))
      (node (ref "R2_BAT") (pin "1") (pinfunction "1_1") (pintype "passive"))
      (node (ref "R4") (pin "1") (pinfunction "1_1") (pintype "passive"))
      (node (ref "RESET_BUTTON") (pin "1") (pinfunction "1_1") (pintype "passive"))
      (node (ref "RESET_BUTTON") (pin "2") (pinfunction "2_2") (pintype "passive"))
      (node (ref "SENSOR2") (pin "1") (pinfunction "GND_1") (pintype "power_in"))
      (node (ref "SENSOR2") (pin "5") (pinfunction "SDO_5") (pintype "bidirectional"))
      (node (ref "SENSOR2") (pin "7") (pinfunction "GND_7") (pintype "power_in"))
      (node (ref "SJ1") (pin "1") (pinfunction "1_1") (pintype "passive"))
      (node (ref "TP5") (pin "TP") (pinfunction "TP_TP") (pintype "input"))
      (node (ref "U1") (pin "4") (pinfunction "GND_4") (pintype "power_in"))
      (node (ref "U1") (pin "9") (pinfunction "EXP_9") (pintype "passive"))
      (node (ref "U2") (pin "1") (pinfunction "GND_1") (pintype "power_in"))
      (node (ref "U2") (pin "28") (pinfunction "GND_28") (pintype "power_in"))
      (node (ref "U2") (pin "29_1") (pinfunction "GND_29_1") (pintype "power_in"))
      (node (ref "U2") (pin "29_2") (pinfunction "GND_29_2") (pintype "power_in"))
      (node (ref "U2") (pin "29_3") (pinfunction "GND_29_3") (pintype "power_in"))
      (node (ref "U2") (pin "29_4") (pinfunction "GND_29_4") (pintype "power_in"))
      (node (ref "U2") (pin "29_5") (pinfunction "GND_29_5") (pintype "power_in"))
      (node (ref "U2") (pin "29_6") (pinfunction "GND_29_6") (pintype "power_in"))
      (node (ref "U2") (pin "29_7") (pinfunction "GND_29_7") (pintype "power_in"))
      (node (ref "U2") (pin "29_8") (pinfunction "GND_29_8") (pintype "power_in"))
      (node (ref "U2") (pin "29_9") (pinfunction "GND_29_9") (pintype "power_in"))
      (node (ref "U3") (pin "13") (pinfunction "GND_13") (pintype "power_in"))
      (node (ref "U4") (pin "1") (pinfunction "CTG_1") (pintype "power_in"))
      (node (ref "U4") (pin "4") (pinfunction "GND_4") (pintype "power_in"))
      (node (ref "U4") (pin "6") (pinfunction "QSTRT_6") (pintype "input"))
      (node (ref "U4") (pin "9") (pinfunction "EP_9") (pintype "power_in"))
    )
    (net (code "14") (name "GPIO8") (class "Default")
      (node (ref "R1") (pin "1") (pinfunction "1_1") (pintype "passive"))
      (node (ref "U2") (pin "10") (pinfunction "IO8_10") (pintype "bidirectional"))
    )
    (net (code "15") (name "I2C_PW") (class "Default")
      (node (ref "C1") (pin "1") (pinfunction "1_1") (pintype "passive"))
      (node (ref "C2") (pin "1") (pinfunction "1_1") (pintype "passive"))
      (node (ref "R1_PINH") (pin "2") (pinfunction "2_2") (pintype "passive"))
      (node (ref "R2_PINH") (pin "2") (pinfunction "2_2") (pintype "passive"))
      (node (ref "SENSOR2") (pin "6") (pinfunction "VDDIO_6") (pintype "power_in"))
      (node (ref "U2") (pin "17") (pinfunction "IO19_17") (pintype "bidirectional"))
    )
    (net (code "16") (name "INT_RTC") (class "Default")
      (node (ref "INT_RTC") (pin "TP") (pinfunction "TP_TP") (pintype "input"))
      (node (ref "R1_PINH1") (pin "1") (pinfunction "1_1") (pintype "passive"))
      (node (ref "U2") (pin "8") (pinfunction "IO0_8") (pintype "bidirectional"))
      (node (ref "U3") (pin "3") (pinfunction "SQW/~{INT}_3") (pintype "output"))
    )
    (net (code "17") (name "IO{slash}BOOT") (class "Default")
      (node (ref "BOOT_BUTTON") (pin "3") (pinfunction "3_3") (pintype "passive"))
      (node (ref "BOOT_BUTTON") (pin "4") (pinfunction "4_4") (pintype "passive"))
      (node (ref "C6") (pin "1") (pinfunction "1_1") (pintype "passive"))
      (node (ref "R_BOOT") (pin "1") (pinfunction "1_1") (pintype "passive"))
      (node (ref "U2") (pin "15") (pinfunction "IO9_15") (pintype "bidirectional"))
    )
    (net (code "18") (name "IO{slash}CHANGE") (class "Default")
      (node (ref "C10") (pin "1") (pinfunction "1_1") (pintype "passive"))
      (node (ref "CHANGE_BUTTON") (pin "3") (pinfunction "3_3") (pintype "passive"))
      (node (ref "CHANGE_BUTTON") (pin "4") (pinfunction "4_4") (pintype "passive"))
      (node (ref "R_CHANGE") (pin "1") (pinfunction "1_1") (pintype "passive"))
      (node (ref "U2") (pin "23") (pinfunction "IO15_23") (pintype "bidirectional"))
    )
    (net (code "19") (name "MISO") (class "Default")
      (node (ref "D12") (pin "2") (pinfunction "2_2") (pintype "passive"))
      (node (ref "J4") (pin "P7") (pinfunction "DAT0_P7") (pintype "bidirectional"))
      (node (ref "MISO") (pin "TP") (pinfunction "TP_TP") (pintype "input"))
      (node (ref "R8") (pin "1") (pinfunction "1_1") (pintype "passive"))
      (node (ref "U1") (pin "2") (pinfunction "DO(IO1)_2") (pintype "bidirectional"))
      (node (ref "U2") (pin "27") (pinfunction "IO2_27") (pintype "bidirectional"))
    )
    (net (code "20") (name "MOSI") (class "Default")
      (node (ref "D11") (pin "2") (pinfunction "2_2") (pintype "passive"))
      (node (ref "J1") (pin "14") (pinfunction "14_14") (pintype "bidirectional"))
      (node (ref "J4") (pin "P3") (pinfunction "CMD_P3") (pintype "bidirectional"))
      (node (ref "MOSI") (pin "TP") (pinfunction "TP_TP") (pintype "input"))
      (node (ref "R7") (pin "1") (pinfunction "1_1") (pintype "passive"))
      (node (ref "U1") (pin "5") (pinfunction "DI(IO0)_5") (pintype "bidirectional"))
      (node (ref "U2") (pin "7") (pinfunction "IO7_7") (pintype "bidirectional"))
    )
    (net (code "21") (name "N$4") (class "Default")
      (node (ref "C7") (pin "1") (pinfunction "1_1") (pintype "passive"))
      (node (ref "L1") (pin "2") (pinfunction "2_2") (pintype "passive"))
    )
    (net (code "22") (name "Net-(CHG_LED-PadC)") (class "Default")
      (node (ref "CHG_LED") (pin "C") (pinfunction "C_C") (pintype "passive"))
      (node (ref "R1_BAT") (pin "1") (pinfunction "1_1") (pintype "passive"))
    )
    (net (code "23") (name "Net-(D2-CATHODE)") (class "Default")
      (node (ref "C1_BAT1") (pin "1") (pinfunction "1_1") (pintype "passive"))
      (node (ref "D2") (pin "1") (pinfunction "CATHODE_1") (pintype "bidirectional"))
      (node (ref "IC4") (pin "1") (pinfunction "VIN_1") (pintype "bidirectional"))
      (node (ref "IC4") (pin "3") (pinfunction "CE_3") (pintype "bidirectional"))
      (node (ref "Q1") (pin "2") (pinfunction "S_2") (pintype "bidirectional"))
    )
    (net (code "24") (name "Net-(D3-A)") (class "Default")
      (node (ref "C4") (pin "1") (pinfunction "1_1") (pintype "passive"))
      (node (ref "D3") (pin "2") (pinfunction "A_2") (pintype "bidirectional"))
      (node (ref "D4") (pin "1") (pinfunction "K_1") (pintype "bidirectional"))
    )
    (net (code "25") (name "Net-(D7-CATHODE)") (class "Default")
      (node (ref "D7") (pin "1") (pinfunction "CATHODE_1") (pintype "bidirectional"))
      (node (ref "R_CAPACITOR") (pin "1") (pinfunction "1_1") (pintype "passive"))
    )
    (net (code "26") (name "Net-(EPD_C1-Pad2)") (class "Default")
      (node (ref "EPD_C1") (pin "2") (pinfunction "2_2") (pintype "passive"))
      (node (ref "J1") (pin "4") (pinfunction "4_4") (pintype "bidirectional"))
    )
    (net (code "27") (name "Net-(EPD_C2-Pad2)") (class "Default")
      (node (ref "EPD_C2") (pin "2") (pinfunction "2_2") (pintype "passive"))
      (node (ref "J1") (pin "5") (pinfunction "5_5") (pintype "bidirectional"))
    )
    (net (code "28") (name "Net-(EPD_C6-Pad2)") (class "Default")
      (node (ref "EPD_C6") (pin "2") (pinfunction "2_2") (pintype "passive"))
      (node (ref "J1") (pin "18") (pinfunction "18_18") (pintype "bidirectional"))
    )
    (net (code "29") (name "Net-(EPD_C7-Pad2)") (class "Default")
      (node (ref "EPD_C7") (pin "2") (pinfunction "2_2") (pintype "passive"))
      (node (ref "J1") (pin "19") (pinfunction "19_19") (pintype "bidirectional"))
    )
    (net (code "30") (name "Net-(EPD_C8-Pad2)") (class "Default")
      (node (ref "EPD_C8") (pin "2") (pinfunction "2_2") (pintype "passive"))
      (node (ref "J1") (pin "20") (pinfunction "20_20") (pintype "bidirectional"))
    )
    (net (code "31") (name "Net-(EPD_C10-Pad2)") (class "Default")
      (node (ref "EPD_C10") (pin "2") (pinfunction "2_2") (pintype "passive"))
      (node (ref "J1") (pin "22") (pinfunction "22_22") (pintype "bidirectional"))
    )
    (net (code "32") (name "Net-(EPD_C12-Pad2)") (class "Default")
      (node (ref "EPD_C12") (pin "2") (pinfunction "2_2") (pintype "passive"))
      (node (ref "J1") (pin "24") (pinfunction "24_24") (pintype "bidirectional"))
    )
    (net (code "33") (name "Net-(IC1-CT)") (class "Default")
      (node (ref "C_DELAY") (pin "1") (pinfunction "1_1") (pintype "passive"))
      (node (ref "IC1") (pin "5") (pinfunction "CT_5") (pintype "bidirectional"))
    )
    (net (code "34") (name "Net-(J2-PadA5)") (class "Default")
      (node (ref "J2") (pin "A5") (pinfunction "A5_A5") (pintype "bidirectional"))
      (node (ref "R2-USB1") (pin "2") (pinfunction "2_2") (pintype "passive"))
    )
    (net (code "35") (name "Net-(J2-PadB5)") (class "Default")
      (node (ref "J2") (pin "B5") (pinfunction "B5_B5") (pintype "bidirectional"))
      (node (ref "R2-USB") (pin "1") (pinfunction "1_1") (pintype "passive"))
    )
    (net (code "36") (name "Net-(MCP73831-PROG)") (class "Default")
      (node (ref "MCP73831") (pin "5") (pinfunction "PROG_5") (pintype "input"))
      (node (ref "R2_BAT") (pin "2") (pinfunction "2_2") (pintype "passive"))
    )
    (net (code "37") (name "Net-(MCP73831-STAT)") (class "Default")
      (node (ref "MCP73831") (pin "1") (pinfunction "STAT_1") (pintype "output"))
      (node (ref "R1_BAT") (pin "2") (pinfunction "2_2") (pintype "passive"))
    )
    (net (code "38") (name "Net-(SENSOR2-CSB)") (class "Default")
      (node (ref "SENSOR2") (pin "2") (pinfunction "CSB_2") (pintype "input"))
      (node (ref "SENSOR2") (pin "8") (pinfunction "VDD_8") (pintype "power_in"))
    )
    (net (code "39") (name "PREVGH") (class "Default")
      (node (ref "D5") (pin "1") (pinfunction "K_1") (pintype "bidirectional"))
      (node (ref "EPD_C9") (pin "2") (pinfunction "2_2") (pintype "passive"))
      (node (ref "J1") (pin "21") (pinfunction "21_21") (pintype "bidirectional"))
    )
    (net (code "40") (name "PREVGL") (class "Default")
      (node (ref "D4") (pin "2") (pinfunction "A_2") (pintype "bidirectional"))
      (node (ref "EPD_C11") (pin "2") (pinfunction "2_2") (pintype "passive"))
      (node (ref "J1") (pin "23") (pinfunction "23_23") (pintype "bidirectional"))
    )
    (net (code "41") (name "RESE") (class "Default")
      (node (ref "J1") (pin "3") (pinfunction "3_3") (pintype "bidirectional"))
      (node (ref "Q3") (pin "2") (pinfunction "S_2") (pintype "bidirectional"))
      (node (ref "R3") (pin "2") (pinfunction "2_2") (pintype "passive"))
    )
    (net (code "42") (name "RESE'") (class "Default")
      (node (ref "R2") (pin "2") (pinfunction "2_2") (pintype "passive"))
      (node (ref "R3") (pin "1") (pinfunction "1_1") (pintype "passive"))
      (node (ref "SJ1") (pin "2") (pinfunction "2_2") (pintype "passive"))
    )
    (net (code "43") (name "RESET") (class "Default")
      (node (ref "C5") (pin "1") (pinfunction "1_1") (pintype "passive"))
      (node (ref "IC1") (pin "1") (pinfunction "VOUT_1") (pintype "bidirectional"))
      (node (ref "RESET_BUTTON") (pin "3") (pinfunction "3_3") (pintype "passive"))
      (node (ref "RESET_BUTTON") (pin "4") (pinfunction "4_4") (pintype "passive"))
      (node (ref "R_RESET") (pin "1") (pinfunction "1_1") (pintype "passive"))
      (node (ref "U2") (pin "3") (pinfunction "EN_3") (pintype "input"))
    )
    (net (code "44") (name "RTC_RST") (class "Default")
      (node (ref "U2") (pin "16") (pinfunction "IO18_16") (pintype "bidirectional"))
      (node (ref "U3") (pin "4") (pinfunction "~{RST}_4") (pintype "input"))
    )
    (net (code "45") (name "RX") (class "Default")
      (node (ref "RX") (pin "TP") (pinfunction "TP_TP") (pintype "input"))
      (node (ref "U2") (pin "24") (pinfunction "RXD0/GPIO17_24") (pintype "bidirectional"))
    )
    (net (code "46") (name "SCK") (class "Default")
      (node (ref "D10") (pin "2") (pinfunction "2_2") (pintype "passive"))
      (node (ref "J1") (pin "13") (pinfunction "13_13") (pintype "bidirectional"))
      (node (ref "J4") (pin "P5") (pinfunction "CLK_P5") (pintype "bidirectional"))
      (node (ref "R6") (pin "1") (pinfunction "1_1") (pintype "passive"))
      (node (ref "SCK1") (pin "TP") (pinfunction "TP_TP") (pintype "input"))
      (node (ref "U1") (pin "6") (pinfunction "CLK_6") (pintype "input"))
      (node (ref "U2") (pin "6") (pinfunction "IO6_6") (pintype "bidirectional"))
    )
    (net (code "47") (name "SCL") (class "Default")
      (node (ref "J3") (pin "4") (pinfunction "4_4") (pintype "passive"))
      (node (ref "R2_PINH") (pin "1") (pinfunction "1_1") (pintype "passive"))
      (node (ref "SENSOR2") (pin "4") (pinfunction "SCK_4") (pintype "input"))
      (node (ref "U2") (pin "20") (pinfunction "IO22_20") (pintype "bidirectional"))
      (node (ref "U3") (pin "16") (pinfunction "SCL_16") (pintype "input"))
      (node (ref "U4") (pin "7") (pinfunction "SCL_7") (pintype "input"))
    )
    (net (code "48") (name "SDA") (class "Default")
      (node (ref "J3") (pin "3") (pinfunction "3_3") (pintype "passive"))
      (node (ref "R1_PINH") (pin "1") (pinfunction "1_1") (pintype "passive"))
      (node (ref "SENSOR2") (pin "3") (pinfunction "SDI_3") (pintype "bidirectional"))
      (node (ref "U2") (pin "19") (pinfunction "IO21_19") (pintype "bidirectional"))
      (node (ref "U3") (pin "15") (pinfunction "SDA_15") (pintype "bidirectional"))
      (node (ref "U4") (pin "8") (pinfunction "SDA_8") (pintype "bidirectional"))
    )
    (net (code "49") (name "SRC") (class "Default")
      (node (ref "C4") (pin "2") (pinfunction "2_2") (pintype "passive"))
      (node (ref "D5") (pin "2") (pinfunction "A_2") (pintype "bidirectional"))
      (node (ref "L1") (pin "1") (pinfunction "1_1") (pintype "passive"))
      (node (ref "Q3") (pin "3") (pinfunction "D_3") (pintype "bidirectional"))
    )
    (net (code "50") (name "SS_SD") (class "Default")
      (node (ref "D8") (pin "2") (pinfunction "2_2") (pintype "passive"))
      (node (ref "J4") (pin "P2") (pinfunction "CD/DAT3_P2") (pintype "bidirectional"))
      (node (ref "R10") (pin "1") (pinfunction "1_1") (pintype "passive"))
      (node (ref "U2") (pin "4") (pinfunction "IO4_4") (pintype "bidirectional"))
    )
    (net (code "51") (name "TX") (class "Default")
      (node (ref "TX") (pin "TP") (pinfunction "TP_TP") (pintype "input"))
      (node (ref "U2") (pin "25") (pinfunction "TXD0/GPIO16_25") (pintype "bidirectional"))
    )
    (net (code "52") (name "USB_D+") (class "Default")
      (node (ref "D1") (pin "1") (pinfunction "I/O1_1_1") (pintype "bidirectional"))
      (node (ref "U2") (pin "14") (pinfunction "IO13_14") (pintype "bidirectional"))
    )
    (net (code "53") (name "USB_D-") (class "Default")
      (node (ref "D1") (pin "3") (pinfunction "I/O2_1_3") (pintype "bidirectional"))
      (node (ref "U2") (pin "13") (pinfunction "IO12_13") (pintype "bidirectional"))
    )
    (net (code "54") (name "VBAT") (class "Default")
      (node (ref "C2_BAT") (pin "1") (pinfunction "1_1") (pintype "passive"))
      (node (ref "MCP73831") (pin "3") (pinfunction "VBAT_3") (pintype "power_in"))
      (node (ref "Q1") (pin "3") (pinfunction "D_3") (pintype "bidirectional"))
      (node (ref "U4") (pin "2") (pinfunction "CELL_2") (pintype "power_in"))
      (node (ref "U4") (pin "3") (pinfunction "VDD_3") (pintype "power_in"))
      (node (ref "VBAT") (pin "TP") (pinfunction "TP_TP") (pintype "input"))
    )
    (net (code "55") (name "VBUS") (class "Default")
      (node (ref "C1_BAT") (pin "1") (pinfunction "1_1") (pintype "passive"))
      (node (ref "C4_USB") (pin "1") (pinfunction "1_1") (pintype "passive"))
      (node (ref "C5_USB") (pin "1") (pinfunction "1_1") (pintype "passive"))
      (node (ref "CHG_LED") (pin "A") (pinfunction "A_A") (pintype "passive"))
      (node (ref "D1") (pin "5") (pinfunction "VBUS_5") (pintype "bidirectional"))
      (node (ref "D2") (pin "2") (pinfunction "ANODE_2") (pintype "bidirectional"))
      (node (ref "MCP73831") (pin "4") (pinfunction "VIN_4") (pintype "power_in"))
      (node (ref "PFMF.050.1") (pin "2") (pinfunction "2_2") (pintype "passive"))
      (node (ref "Q1") (pin "1") (pinfunction "G_1") (pintype "bidirectional"))
      (node (ref "R1_PWRUSB") (pin "1") (pinfunction "1_1") (pintype "passive"))
      (node (ref "VBUS") (pin "TP") (pinfunction "TP_TP") (pintype "input"))
    )
    (net (code "56") (name "VRTC") (class "Default")
      (node (ref "C10_SUPERCAP") (pin "2") (pinfunction "2_2") (pintype "passive"))
      (node (ref "C8") (pin "1") (pinfunction "1_1") (pintype "passive"))
      (node (ref "R_CAPACITOR") (pin "2") (pinfunction "2_2") (pintype "passive"))
      (node (ref "U3") (pin "14") (pinfunction "VBAT_14") (pintype "power_in"))
    )
    (net (code "57") (name "VUSB") (class "Default")
      (node (ref "J2") (pin "A4") (pinfunction "A4_A4") (pintype "bidirectional"))
      (node (ref "J2") (pin "A9") (pinfunction "A9_A9") (pintype "bidirectional"))
      (node (ref "J2") (pin "B4") (pinfunction "B4_B4") (pintype "bidirectional"))
      (node (ref "J2") (pin "B9") (pinfunction "B9_B9") (pintype "bidirectional"))
      (node (ref "PFMF.050.1") (pin "1") (pinfunction "1_1") (pintype "passive"))
    )
    (net (code "58") (name "unconnected-(IC1-NC-Pad4)") (class "Default")
      (node (ref "IC1") (pin "4") (pinfunction "NC_4") (pintype "no_connect"))
    )
    (net (code "59") (name "unconnected-(IC4-NC-Pad4)") (class "Default")
      (node (ref "IC4") (pin "4") (pinfunction "NC_4") (pintype "no_connect"))
    )
    (net (code "60") (name "unconnected-(J1-Pad1)") (class "Default")
      (node (ref "J1") (pin "1") (pinfunction "1_1") (pintype "bidirectional"))
    )
    (net (code "61") (name "unconnected-(J1-Pad6)") (class "Default")
      (node (ref "J1") (pin "6") (pinfunction "6_6") (pintype "bidirectional"))
    )
    (net (code "62") (name "unconnected-(J1-Pad7)") (class "Default")
      (node (ref "J1") (pin "7") (pinfunction "7_7") (pintype "bidirectional"))
    )
    (net (code "63") (name "unconnected-(J2-PadA8)") (class "Default")
      (node (ref "J2") (pin "A8") (pinfunction "A8_A8") (pintype "bidirectional"))
    )
    (net (code "64") (name "unconnected-(J2-PadB8)") (class "Default")
      (node (ref "J2") (pin "B8") (pinfunction "B8_B8") (pintype "bidirectional"))
    )
    (net (code "65") (name "unconnected-(J4-DAT1-PadP8)") (class "Default")
      (node (ref "J4") (pin "P8") (pinfunction "DAT1_P8") (pintype "bidirectional"))
    )
    (net (code "66") (name "unconnected-(J4-DAT2-PadP1)") (class "Default")
      (node (ref "J4") (pin "P1") (pinfunction "DAT2_P1") (pintype "bidirectional"))
    )
    (net (code "67") (name "unconnected-(J4-DETECTION_1-PadS1)") (class "Default")
      (node (ref "J4") (pin "S1") (pinfunction "DETECTION_1_S1") (pintype "bidirectional"))
    )
    (net (code "68") (name "unconnected-(J4-DETECTION_2-PadS2)") (class "Default")
      (node (ref "J4") (pin "S2") (pinfunction "DETECTION_2_S2") (pintype "bidirectional"))
    )
    (net (code "69") (name "unconnected-(U2-NC-Pad22)") (class "Default")
      (node (ref "U2") (pin "22") (pinfunction "NC_22") (pintype "no_connect"))
    )
    (net (code "70") (name "unconnected-(U4-~{ALERT}-Pad5)") (class "Default")
      (node (ref "U4") (pin "5") (pinfunction "~{ALERT}_5") (pintype "output"))
    )
  )
)
